# LC.net
KiCad netlist of a schematic drawn in Altium Designer
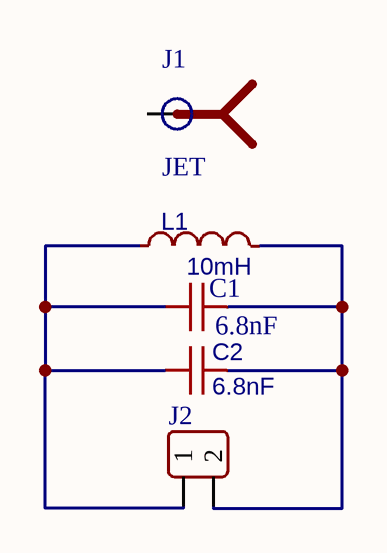
[diagram p0: LC.SchDoc]

(export (version "E")
  (design (tool "Eeschema 10.0.6"))
  (components
    (comp (ref "C1") (value "6.8nF") (footprint "CAP3") (libsource (lib "LTC_Library1") (part "CAP_聚苯电容")))
    (comp (ref "C2")
      (value "6.8nF")
      (footprint "CAP_0603")
      (fields
        (field (name "BOM_SUPPLIER PART") "C307348")
        (field (name "BOM_MANUFACTURER PART") "CL10B104KB8WPNC")
        (field (name "CONTRIBUTOR") "LCSC")
      )
      (libsource (lib "LTC_Library1") (part "CAP_0603"))
    )
    (comp (ref "J1")
      (value "JET")
      (footprint "M_KONG_springChange")
      (libsource (lib "LTC_Library1") (part "JET"))
    )
    (comp (ref "J2")
      (value "Header")
      (footprint "Header H 2.54X2")
      (libsource (lib "LTC_Library1") (part "Header 2.54_2"))
    )
    (comp (ref "L1")
      (value "10mH")
      (footprint "Inductor_8x10")
      (fields
        (field (name "BOM_SUPPLIER PART") "C295130")
        (field (name "BOM_MANUFACTURER PART") "NLV25T-330J-EF")
        (field (name "CONTRIBUTOR") "LCSC")
      )
      (libsource (lib "LTC_Library1") (part "Inductor"))
    )
  )
  (nets
    (net (code "1") (name "Net-(C1-Pad1)") (class "Default")
      (node (ref "C1") (pin "1") (pinfunction "1_1") (pintype "passive"))
      (node (ref "C2") (pin "1") (pinfunction "1_1") (pintype "passive"))
      (node (ref "J2") (pin "1") (pinfunction "1_1") (pintype "passive"))
      (node (ref "L1") (pin "1") (pinfunction "1_1") (pintype "passive"))
    )
    (net (code "2") (name "Net-(C1-Pad2)") (class "Default")
      (node (ref "C1") (pin "2") (pinfunction "2_2") (pintype "passive"))
      (node (ref "C2") (pin "2") (pinfunction "2_2") (pintype "passive"))
      (node (ref "J2") (pin "2") (pinfunction "2_2") (pintype "passive"))
      (node (ref "L1") (pin "2") (pinfunction "2_2") (pintype "passive"))
    )
    (net (code "3") (name "unconnected-(J1-Pad1)") (class "Default")
      (node (ref "J1") (pin "1") (pintype "passive"))
    )
  )
)
